# yard-ice-toplevel.net
KiCad netlist of a schematic drawn in Altium Designer
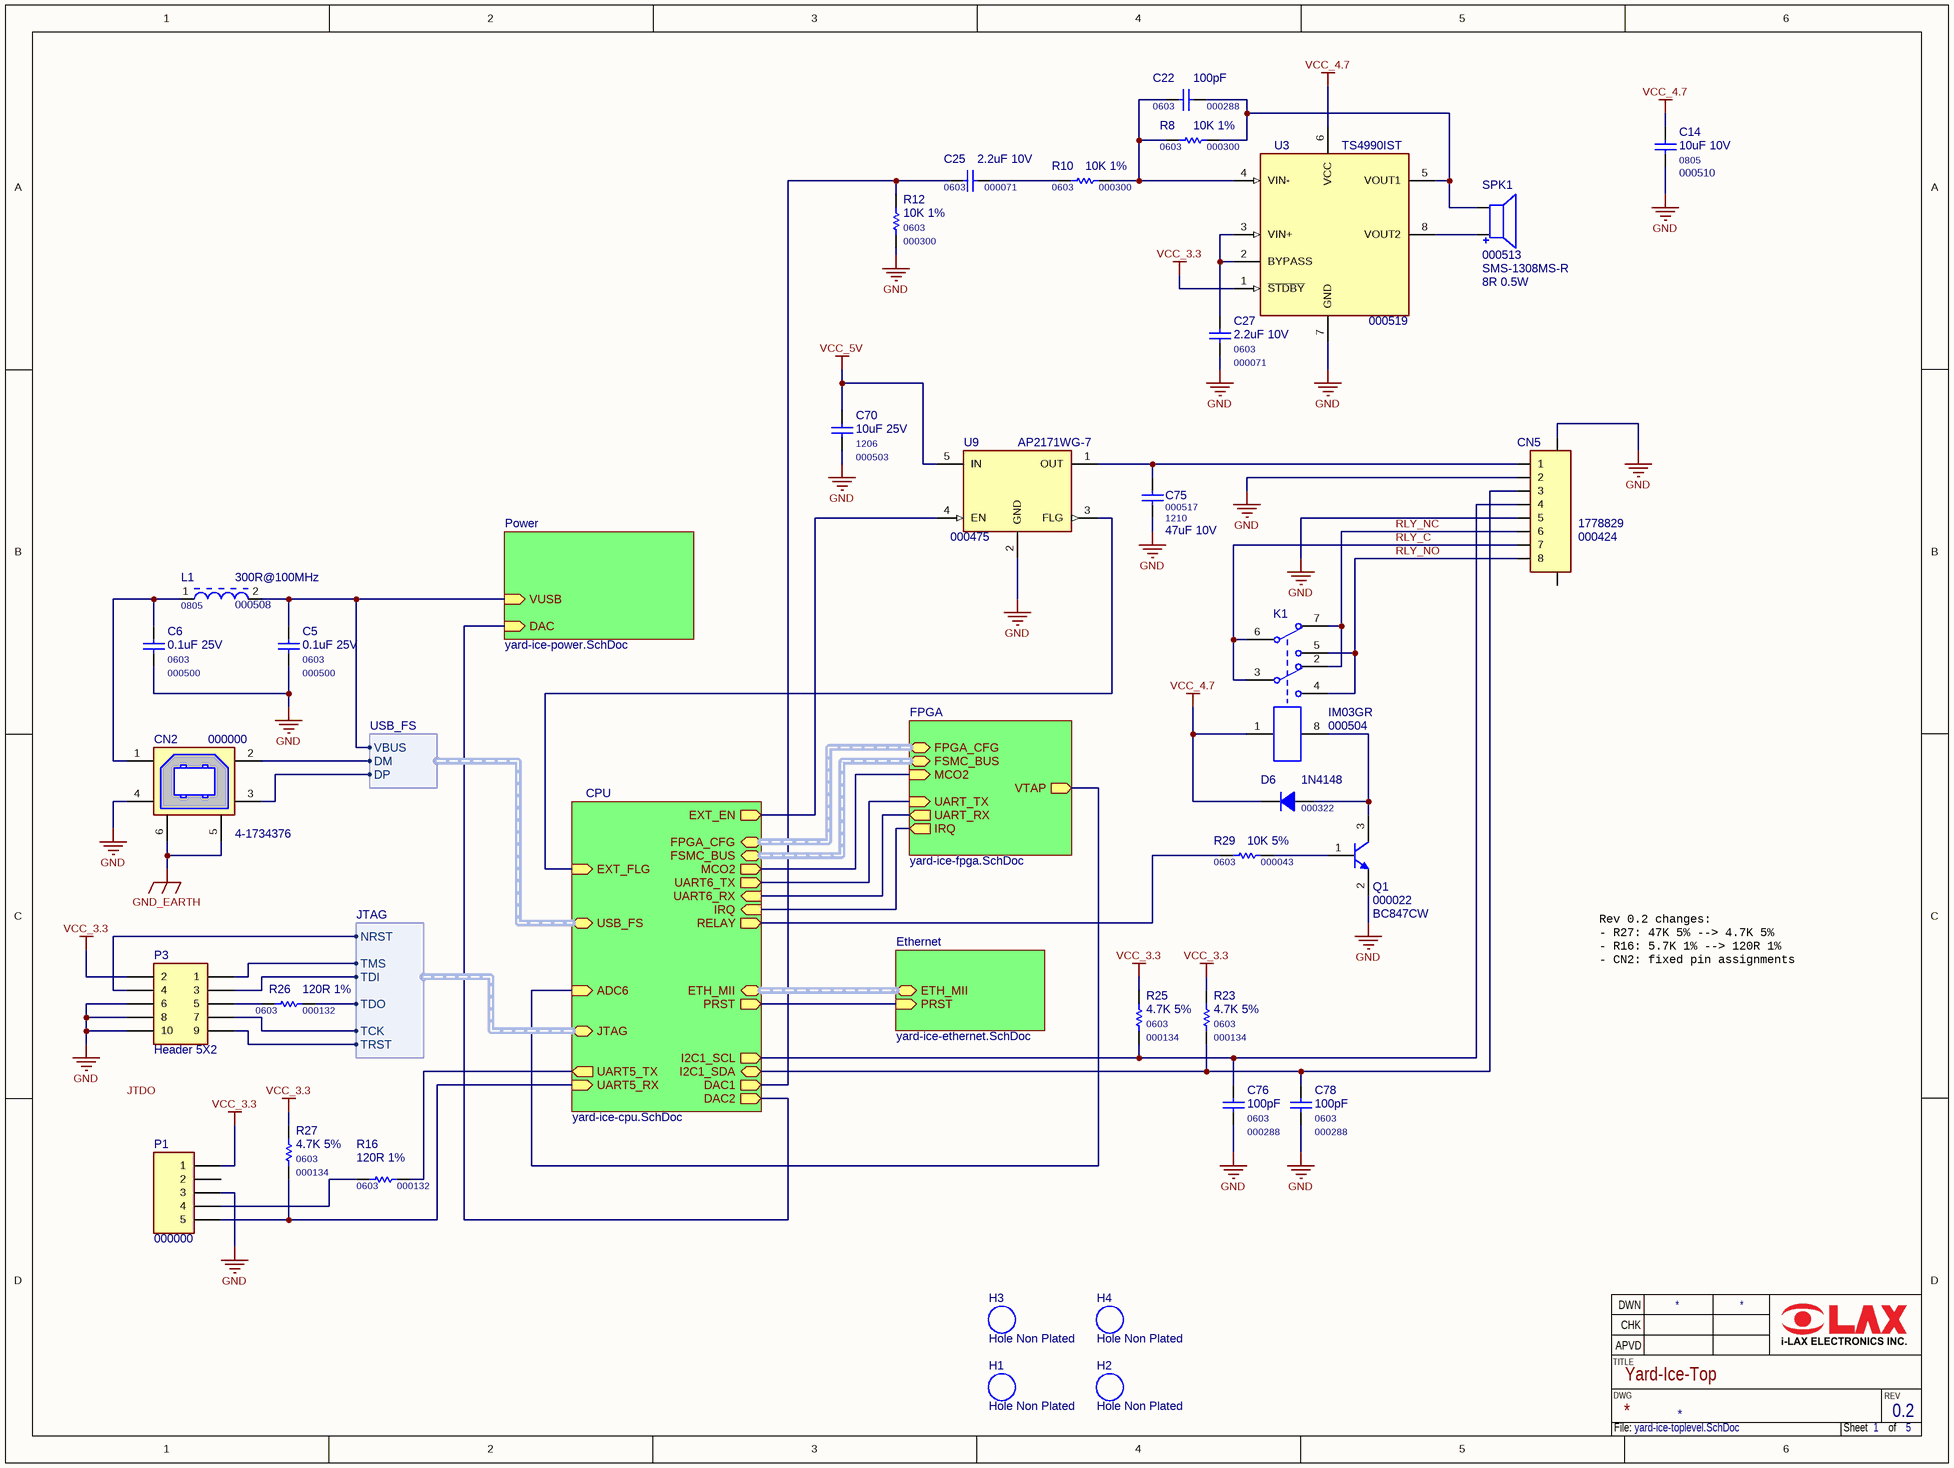
[diagram p0: yard-ice-toplevel.SchDoc]

(export (version "E")
  (design (tool "Eeschema 10.0.6"))
  (components
    (comp (ref "C5")
      (value "000500")
      (footprint "C0603M")
      (description "SMD Ceramic Chip Capacitor - 0603 - X7R")
      (fields
        (field (name "ALTIUM_VALUE") "0.1uF 25V")
        (field (name "PACKAGE") "0603")
        (field (name "MF") "TDK")
      )
      (libsource (lib "discrete-sm") (part "C0603"))
    )
    (comp (ref "C6")
      (value "000500")
      (footprint "C0603M")
      (description "SMD Ceramic Chip Capacitor - 0603 - X7R")
      (fields
        (field (name "ALTIUM_VALUE") "0.1uF 25V")
        (field (name "PACKAGE") "0603")
        (field (name "MF") "TDK")
      )
      (libsource (lib "discrete-sm") (part "C0603"))
    )
    (comp (ref "C14")
      (value "000510")
      (footprint "C0805M")
      (description "SMD Ceramic Chip Capacitor - 0805 - X7R")
      (fields
        (field (name "ALTIUM_VALUE") "10uF 10V")
        (field (name "PACKAGE") "0805")
        (field (name "MF") "TDK")
      )
      (libsource (lib "sm_cap") (part "C0805"))
    )
    (comp (ref "C22")
      (value "000288")
      (footprint "C0603M")
      (description "SMD Ceramic Chip Capacitor - 0603")
      (fields (field (name "ALTIUM_VALUE") "100pF") (field (name "PACKAGE") "0603"))
      (libsource (lib "discrete-sm") (part "C0603"))
    )
    (comp (ref "C25")
      (value "000071")
      (footprint "C0603M")
      (description "SMD Ceramic Chip Capacitor - 0603 - X7R")
      (fields
        (field (name "ALTIUM_VALUE") "2.2uF 10V")
        (field (name "PACKAGE") "0603")
        (field (name "MF") "Taiyo Yuden")
      )
      (libsource (lib "discrete-sm") (part "C0603"))
    )
    (comp (ref "C27")
      (value "000071")
      (footprint "C0603M")
      (description "SMD Ceramic Chip Capacitor - 0603 - X7R")
      (fields
        (field (name "ALTIUM_VALUE") "2.2uF 10V")
        (field (name "PACKAGE") "0603")
        (field (name "MF") "Taiyo Yuden")
      )
      (libsource (lib "discrete-sm") (part "C0603"))
    )
    (comp (ref "C70")
      (value "000503")
      (footprint "C1206M")
      (description "SMD Ceramic Chip Capacitor - 1206 - X7R")
      (fields
        (field (name "ALTIUM_VALUE") "10uF 25V")
        (field (name "PACKAGE") "1206")
        (field (name "MF") "Taiyo Yuden")
      )
      (libsource (lib "discrete-sm") (part "C1206"))
    )
    (comp (ref "C75")
      (value "000517")
      (footprint "C1210M")
      (description "SMD Ceramic Chip Capacitor - 1210 - X7R")
      (fields
        (field (name "PACKAGE") "1210")
        (field (name "ALTIUM_VALUE") "47uF 10V")
        (field (name "MF") "Taiyo Yuden")
      )
      (libsource (lib "discrete-sm") (part "C12010"))
    )
    (comp (ref "C76")
      (value "000288")
      (footprint "C0603M")
      (description "SMD Ceramic Chip Capacitor - 0603")
      (fields (field (name "ALTIUM_VALUE") "100pF") (field (name "PACKAGE") "0603"))
      (libsource (lib "discrete-sm") (part "C0603"))
    )
    (comp (ref "C78")
      (value "000288")
      (footprint "C0603M")
      (description "SMD Ceramic Chip Capacitor - 0603")
      (fields (field (name "ALTIUM_VALUE") "100pF") (field (name "PACKAGE") "0603"))
      (libsource (lib "discrete-sm") (part "C0603"))
    )
    (comp (ref "CN2")
      (value "000000")
      (footprint "4-1734376")
      (description "USB Type B - Right Angle - Thru Hole")
      (fields (field (name "ALTIUM_VALUE") "4-1734376") (field (name "MF") "Tyco"))
      (libsource (lib "tyco-conn") (part "4-1734376"))
    )
    (comp (ref "CN5")
      (value "000424")
      (footprint "1778829")
      (description "Terminal Block, Header, 8-Pos")
      (fields (field (name "ALTIUM_VALUE") "1778829") (field (name "MF") "Phoenix Contacts"))
      (libsource (lib "phoenix-contact") (part "Combicon SMT 8"))
    )
    (comp (ref "D6")
      (value "000322")
      (footprint "SOD-123")
      (description "Schottky Barrier Diode")
      (fields (field (name "MF") "Diodes Inc") (field (name "ALTIUM_VALUE") "1N4148"))
      (libsource (lib "diodes-inc") (part "1N4148W"))
    )
    (comp (ref "H1")
      (value "Hole Non Plated")
      (footprint "Hole NP 3.2x5.0x5.0")
      (libsource (lib "mechanical") (part "Hole Non Plated"))
    )
    (comp (ref "H2")
      (value "Hole Non Plated")
      (footprint "Hole NP 3.2x5.0x5.0")
      (libsource (lib "mechanical") (part "Hole Non Plated"))
    )
    (comp (ref "H3")
      (value "Hole Non Plated")
      (footprint "Hole NP 3.2x5.0x5.0")
      (libsource (lib "mechanical") (part "Hole Non Plated"))
    )
    (comp (ref "H4")
      (value "Hole Non Plated")
      (footprint "Hole NP 3.2x5.0x5.0")
      (libsource (lib "mechanical") (part "Hole Non Plated"))
    )
    (comp (ref "K1")
      (value "000504")
      (footprint "Relay-10X6")
      (description "Dual-Pole Dual-Throw Relay")
      (fields (field (name "ALTIUM_VALUE") "IM03GR") (field (name "MF") "Tyco"))
      (libsource (lib "sm-electromechanical") (part "Relay-DPDT"))
    )
    (comp (ref "L1")
      (value "000508")
      (footprint "L0805M")
      (description "SMD Chip Inductor - 0805")
      (fields
        (field (name "ALTIUM_VALUE") "300R@100MHz")
        (field (name "PACKAGE") "0805")
        (field (name "MF") "TDK")
      )
      (libsource (lib "discrete-sm") (part "L0805"))
    )
    (comp (ref "P1")
      (value "000000")
      (footprint "TSW-105-07-G-S")
      (description "Header, 5-Pin")
      (libsource (lib "samtec-board-to-board") (part "Header 5"))
    )
    (comp (ref "P3")
      (value "Header 5X2")
      (footprint "TSW-105-07-G-D")
      (description "Header 5-Pin, Dual row")
      (libsource (lib "samtec-board-to-board") (part "Header 5X2"))
    )
    (comp (ref "Q1")
      (value "000022")
      (footprint "SOT-323")
      (description "NPN General-purpose Transistor")
      (fields (field (name "ALTIUM_VALUE") "BC847CW") (field (name "MF") "Diodes Inc"))
      (libsource (lib "diodes-inc") (part "BC847CW"))
    )
    (comp (ref "R8")
      (value "000300")
      (footprint "R0603M")
      (description "SMD Chip Resistor - 0603")
      (fields (field (name "ALTIUM_VALUE") "10K 1%") (field (name "PACKAGE") "0603"))
      (libsource (lib "discrete-sm") (part "R0603"))
    )
    (comp (ref "R10")
      (value "000300")
      (footprint "R0603M")
      (description "SMD Chip Resistor - 0603")
      (fields (field (name "ALTIUM_VALUE") "10K 1%") (field (name "PACKAGE") "0603"))
      (libsource (lib "discrete-sm") (part "R0603"))
    )
    (comp (ref "R12")
      (value "000300")
      (footprint "R0603M")
      (description "SMD Chip Resistor - 0603")
      (fields (field (name "ALTIUM_VALUE") "10K 1%") (field (name "PACKAGE") "0603"))
      (libsource (lib "discrete-sm") (part "R0603"))
    )
    (comp (ref "R16")
      (value "000132")
      (footprint "R0603M")
      (description "SMD Chip Resistor - 0603")
      (fields (field (name "ALTIUM_VALUE") "120R 1%") (field (name "PACKAGE") "0603"))
      (libsource (lib "discrete-sm") (part "R0603"))
    )
    (comp (ref "R23")
      (value "000134")
      (footprint "R0603M")
      (description "SMD Chip Resistor - 0603")
      (fields (field (name "ALTIUM_VALUE") "4.7K 5%") (field (name "PACKAGE") "0603"))
      (libsource (lib "discrete-sm") (part "R0603"))
    )
    (comp (ref "R25")
      (value "000134")
      (footprint "R0603M")
      (description "SMD Chip Resistor - 0603")
      (fields (field (name "ALTIUM_VALUE") "4.7K 5%") (field (name "PACKAGE") "0603"))
      (libsource (lib "discrete-sm") (part "R0603"))
    )
    (comp (ref "R26")
      (value "000132")
      (footprint "R0603M")
      (description "SMD Chip Resistor - 0603")
      (fields (field (name "ALTIUM_VALUE") "120R 1%") (field (name "PACKAGE") "0603"))
      (libsource (lib "discrete-sm") (part "R0603"))
    )
    (comp (ref "R27")
      (value "000134")
      (footprint "R0603M")
      (description "SMD Chip Resistor - 0603")
      (fields (field (name "ALTIUM_VALUE") "4.7K 5%") (field (name "PACKAGE") "0603"))
      (libsource (lib "discrete-sm") (part "R0603"))
    )
    (comp (ref "R29")
      (value "000043")
      (footprint "R0603M")
      (description "SMD Chip Resistor - 0603")
      (fields (field (name "ALTIUM_VALUE") "10K 5%") (field (name "PACKAGE") "0603"))
      (libsource (lib "discrete-sm") (part "R0603"))
    )
    (comp (ref "SPK1")
      (value "000513")
      (footprint "SMS-1308MS-R")
      (description "Loudspeaker")
      (fields
        (field (name "MF") "PUI-Audio")
        (field (name "MF PN") "SMS-1308MS-R")
        (field (name "ALTIUM_VALUE") "8R 0.5W")
      )
      (libsource (lib "pui-audio") (part "SMS-1308MS-R"))
    )
    (comp (ref "U3")
      (value "000519")
      (footprint "MiniSO-8M")
      (description "1.2 W audio power amplifier with active-low standby mode")
      (fields (field (name "ALTIUM_VALUE") "TS4990IST"))
      (libsource (lib "st-audio") (part "TS4990IST"))
    )
    (comp (ref "U9")
      (value "000475")
      (footprint "SOT-25")
      (description "1A SINGLE CHANNEL CURRENT-LIMITED POWER  SWITCH")
      (fields (field (name "ALTIUM_VALUE") "AP2171WG-7") (field (name "MF") "Diodes Inc"))
      (libsource (lib "diodes-inc-pwr-mgmt") (part "AP2171W"))
    )
  )
  (nets
    (net (code "3") (name "/DAC1") (class "Default")
      (node (ref "C25") (pin "1") (pinfunction "1_1") (pintype "passive"))
      (node (ref "R12") (pin "2") (pinfunction "2_2") (pintype "passive"))
    )
    (net (code "6") (name "/EXT_EN") (class "Default")
      (node (ref "U9") (pin "4") (pinfunction "EN_4") (pintype "input"))
    )
    (net (code "7") (name "/EXT_FLG") (class "Default")
      (node (ref "U9") (pin "3") (pinfunction "FLG_3") (pintype "output"))
    )
    (net (code "10") (name "/I2C1_SCL") (class "Default")
      (node (ref "C76") (pin "1") (pinfunction "1_1") (pintype "passive"))
      (node (ref "CN5") (pin "4") (pinfunction "4_4") (pintype "passive"))
      (node (ref "R25") (pin "1") (pinfunction "1_1") (pintype "passive"))
    )
    (net (code "11") (name "/I2C1_SDA") (class "Default")
      (node (ref "C78") (pin "1") (pinfunction "1_1") (pintype "passive"))
      (node (ref "CN5") (pin "3") (pinfunction "3_3") (pintype "passive"))
      (node (ref "R23") (pin "1") (pinfunction "1_1") (pintype "passive"))
    )
    (net (code "16") (name "/RELAY") (class "Default")
      (node (ref "R29") (pin "2") (pinfunction "2_2") (pintype "passive"))
    )
    (net (code "17") (name "/RLY_C") (class "Default")
      (node (ref "CN5") (pin "7") (pinfunction "7_7") (pintype "passive"))
      (node (ref "K1") (pin "3") (pinfunction "3_3") (pintype "passive"))
      (node (ref "K1") (pin "6") (pinfunction "6_6") (pintype "passive"))
    )
    (net (code "18") (name "/RLY_NC") (class "Default")
      (node (ref "CN5") (pin "6") (pinfunction "6_6") (pintype "passive"))
      (node (ref "K1") (pin "2") (pinfunction "2_2") (pintype "passive"))
      (node (ref "K1") (pin "7") (pinfunction "7_7") (pintype "passive"))
    )
    (net (code "19") (name "/RLY_NO") (class "Default")
      (node (ref "CN5") (pin "8") (pinfunction "8_8") (pintype "passive"))
      (node (ref "K1") (pin "4") (pinfunction "4_4") (pintype "passive"))
      (node (ref "K1") (pin "5") (pinfunction "5_5") (pintype "passive"))
    )
    (net (code "20") (name "/UART5_RX") (class "Default")
      (node (ref "P1") (pin "5") (pinfunction "5_5") (pintype "passive"))
      (node (ref "R27") (pin "1") (pinfunction "1_1") (pintype "passive"))
    )
    (net (code "21") (name "/UART5_TX") (class "Default")
      (node (ref "R16") (pin "1") (pinfunction "1_1") (pintype "passive"))
    )
    (net (code "25") (name "/VUSB") (class "Default")
      (node (ref "C5") (pin "1") (pinfunction "1_1") (pintype "passive"))
      (node (ref "L1") (pin "2") (pinfunction "2_2") (pintype "passive"))
    )
    (net (code "28") (name "GND") (class "Default")
      (node (ref "C14") (pin "2") (pinfunction "2_2") (pintype "passive"))
      (node (ref "C27") (pin "2") (pinfunction "2_2") (pintype "passive"))
      (node (ref "C5") (pin "2") (pinfunction "2_2") (pintype "passive"))
      (node (ref "C6") (pin "2") (pinfunction "2_2") (pintype "passive"))
      (node (ref "C70") (pin "2") (pinfunction "2_2") (pintype "passive"))
      (node (ref "C75") (pin "2") (pinfunction "2_2") (pintype "passive"))
      (node (ref "C76") (pin "2") (pinfunction "2_2") (pintype "passive"))
      (node (ref "C78") (pin "2") (pinfunction "2_2") (pintype "passive"))
      (node (ref "CN2") (pin "4") (pinfunction "4_4") (pintype "passive"))
      (node (ref "CN5") (pin "2") (pinfunction "2_2") (pintype "passive"))
      (node (ref "CN5") (pin "5") (pinfunction "5_5") (pintype "passive"))
      (node (ref "CN5") (pin "9") (pinfunction "9_9") (pintype "passive"))
      (node (ref "P1") (pin "3") (pinfunction "3_3") (pintype "passive"))
      (node (ref "P3") (pin "10") (pinfunction "10_10") (pintype "passive"))
      (node (ref "P3") (pin "6") (pinfunction "6_6") (pintype "passive"))
      (node (ref "P3") (pin "8") (pinfunction "8_8") (pintype "passive"))
      (node (ref "Q1") (pin "2") (pinfunction "E_2") (pintype "passive"))
      (node (ref "R12") (pin "1") (pinfunction "1_1") (pintype "passive"))
      (node (ref "U3") (pin "7") (pinfunction "GND_7") (pintype "power_in"))
      (node (ref "U9") (pin "2") (pinfunction "GND_2") (pintype "power_in"))
    )
    (net (code "29") (name "GND_EARTH") (class "Default")
      (node (ref "CN2") (pin "5") (pinfunction "SHIELD_5") (pintype "passive"))
      (node (ref "CN2") (pin "6") (pinfunction "SHIELD_6") (pintype "passive"))
    )
    (net (code "30") (name "Net-(C6-Pad1)") (class "Default")
      (node (ref "C6") (pin "1") (pinfunction "1_1") (pintype "passive"))
      (node (ref "CN2") (pin "1") (pinfunction "1_1") (pintype "passive"))
      (node (ref "L1") (pin "1") (pinfunction "1_1") (pintype "passive"))
    )
    (net (code "31") (name "Net-(C25-Pad2)") (class "Default")
      (node (ref "C25") (pin "2") (pinfunction "2_2") (pintype "passive"))
      (node (ref "R10") (pin "2") (pinfunction "2_2") (pintype "passive"))
    )
    (net (code "32") (name "Net-(D6-A)") (class "Default")
      (node (ref "D6") (pin "1") (pinfunction "A_1") (pintype "passive"))
      (node (ref "K1") (pin "8") (pinfunction "8_8") (pintype "passive"))
      (node (ref "Q1") (pin "3") (pinfunction "C_3") (pintype "passive"))
    )
    (net (code "33") (name "Net-(P1-Pad4)") (class "Default")
      (node (ref "P1") (pin "4") (pinfunction "4_4") (pintype "passive"))
      (node (ref "R16") (pin "2") (pinfunction "2_2") (pintype "passive"))
    )
    (net (code "34") (name "Net-(P3-Pad5)") (class "Default")
      (node (ref "P3") (pin "5") (pinfunction "5_5") (pintype "passive"))
      (node (ref "R26") (pin "1") (pinfunction "1_1") (pintype "passive"))
    )
    (net (code "35") (name "Net-(Q1-B)") (class "Default")
      (node (ref "Q1") (pin "1") (pinfunction "B_1") (pintype "passive"))
      (node (ref "R29") (pin "1") (pinfunction "1_1") (pintype "passive"))
    )
    (net (code "36") (name "Net-(U3-BYPASS)") (class "Default")
      (node (ref "C27") (pin "1") (pinfunction "1_1") (pintype "passive"))
      (node (ref "U3") (pin "2") (pinfunction "BYPASS_2") (pintype "passive"))
      (node (ref "U3") (pin "3") (pinfunction "VIN+_3") (pintype "input"))
    )
    (net (code "37") (name "Net-(U3-VIN-)") (class "Default")
      (node (ref "C22") (pin "1") (pinfunction "1_1") (pintype "passive"))
      (node (ref "R10") (pin "1") (pinfunction "1_1") (pintype "passive"))
      (node (ref "R8") (pin "2") (pinfunction "2_2") (pintype "passive"))
      (node (ref "U3") (pin "4") (pinfunction "VIN-_4") (pintype "input"))
    )
    (net (code "38") (name "Net-(U3-VOUT1)") (class "Default")
      (node (ref "C22") (pin "2") (pinfunction "2_2") (pintype "passive"))
      (node (ref "R8") (pin "1") (pinfunction "1_1") (pintype "passive"))
      (node (ref "SPK1") (pin "2") (pinfunction "2_2") (pintype "passive"))
      (node (ref "U3") (pin "5") (pinfunction "VOUT1_5") (pintype "passive"))
    )
    (net (code "39") (name "Net-(U3-VOUT2)") (class "Default")
      (node (ref "SPK1") (pin "1") (pinfunction "1_1") (pintype "passive"))
      (node (ref "U3") (pin "8") (pinfunction "VOUT2_8") (pintype "passive"))
    )
    (net (code "40") (name "Net-(U9-OUT)") (class "Default")
      (node (ref "C75") (pin "1") (pinfunction "1_1") (pintype "passive"))
      (node (ref "CN5") (pin "1") (pinfunction "1_1") (pintype "passive"))
      (node (ref "U9") (pin "1") (pinfunction "OUT_1") (pintype "power_in"))
    )
    (net (code "41") (name "VCC_3.3") (class "Default")
      (node (ref "P1") (pin "1") (pinfunction "1_1") (pintype "passive"))
      (node (ref "P3") (pin "2") (pinfunction "2_2") (pintype "passive"))
      (node (ref "R23") (pin "2") (pinfunction "2_2") (pintype "passive"))
      (node (ref "R25") (pin "2") (pinfunction "2_2") (pintype "passive"))
      (node (ref "R27") (pin "2") (pinfunction "2_2") (pintype "passive"))
      (node (ref "U3") (pin "1") (pinfunction "~{STDBY}_1") (pintype "input"))
    )
    (net (code "42") (name "VCC_4.7") (class "Default")
      (node (ref "C14") (pin "1") (pinfunction "1_1") (pintype "passive"))
      (node (ref "D6") (pin "2") (pinfunction "K_2") (pintype "passive"))
      (node (ref "K1") (pin "1") (pinfunction "1_1") (pintype "passive"))
      (node (ref "U3") (pin "6") (pinfunction "VCC_6") (pintype "power_in"))
    )
    (net (code "43") (name "VCC_5V") (class "Default")
      (node (ref "C70") (pin "1") (pinfunction "1_1") (pintype "passive"))
      (node (ref "U9") (pin "5") (pinfunction "IN_5") (pintype "power_in"))
    )
    (net (code "44") (name "unconnected-(CN2-Pad2)") (class "Default")
      (node (ref "CN2") (pin "2") (pinfunction "2_2") (pintype "passive"))
    )
    (net (code "45") (name "unconnected-(CN2-Pad3)") (class "Default")
      (node (ref "CN2") (pin "3") (pinfunction "3_3") (pintype "passive"))
    )
    (net (code "46") (name "unconnected-(CN5-Pad10)") (class "Default")
      (node (ref "CN5") (pin "10") (pinfunction "10_10") (pintype "passive"))
    )
    (net (code "47") (name "unconnected-(P1-Pad2)") (class "Default")
      (node (ref "P1") (pin "2") (pinfunction "2_2") (pintype "passive"))
    )
    (net (code "48") (name "unconnected-(P3-Pad1)") (class "Default")
      (node (ref "P3") (pin "1") (pinfunction "1_1") (pintype "passive"))
    )
    (net (code "49") (name "unconnected-(P3-Pad3)") (class "Default")
      (node (ref "P3") (pin "3") (pinfunction "3_3") (pintype "passive"))
    )
    (net (code "50") (name "unconnected-(P3-Pad4)") (class "Default")
      (node (ref "P3") (pin "4") (pinfunction "4_4") (pintype "passive"))
    )
    (net (code "51") (name "unconnected-(P3-Pad7)") (class "Default")
      (node (ref "P3") (pin "7") (pinfunction "7_7") (pintype "passive"))
    )
    (net (code "52") (name "unconnected-(P3-Pad9)") (class "Default")
      (node (ref "P3") (pin "9") (pinfunction "9_9") (pintype "passive"))
    )
    (net (code "53") (name "unconnected-(R26-Pad2)") (class "Default")
      (node (ref "R26") (pin "2") (pinfunction "2_2") (pintype "passive"))
    )
  )
)
